# design.net
KiCad netlist of a schematic drawn in Altium Designer
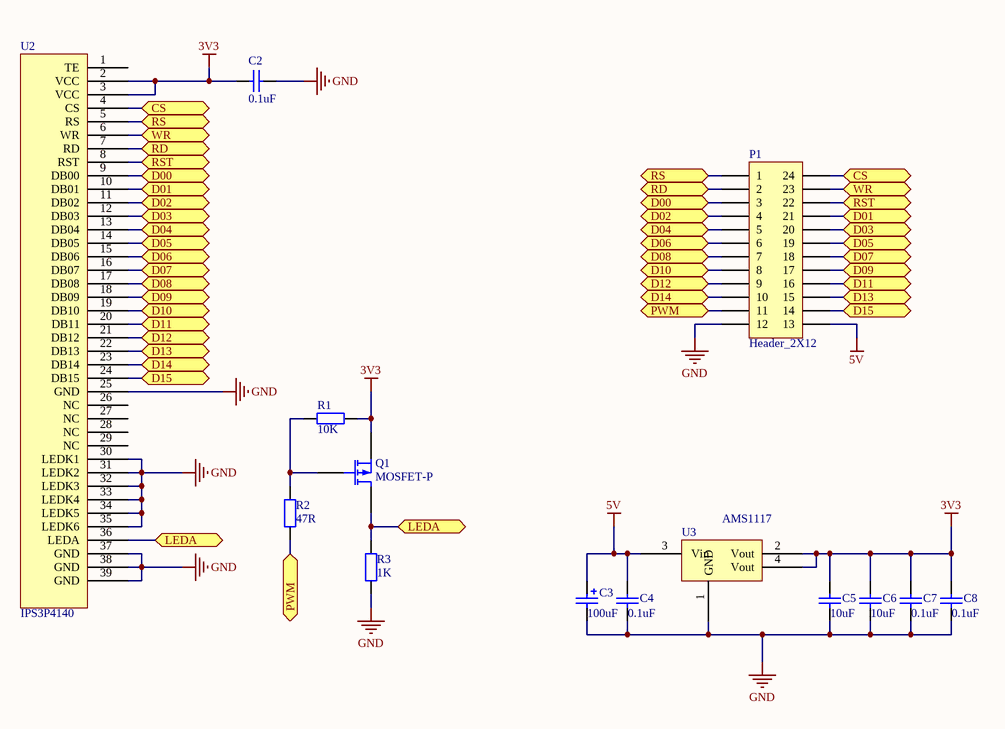
[diagram p0: 液晶板.SchDoc]

(export (version "E")
  (design (tool "Eeschema 10.0.6"))
  (components
    (comp (ref "C2")
      (value "0.1uF")
      (footprint "1608[0603]")
      (description "Capacitor (Semiconductor SIM Model)")
      (fields (field (name "Comment") "Cap Semi") (field (name "PUBLISHER") "Altium Limited"))
      (libsource (lib "Miscellaneous Devices") (part "Cap Semi"))
    )
    (comp (ref "C3")
      (value "100uF")
      (footprint "3528")
      (description "Polarized Capacitor (Axial)")
      (fields (field (name "Comment") "Cap Pol2") (field (name "PUBLISHER") "Altium Limited"))
      (libsource (lib "Miscellaneous Devices") (part "Cap Pol2"))
    )
    (comp (ref "C4")
      (value "0.1uF")
      (footprint "1608[0603]")
      (description "Capacitor (Semiconductor SIM Model)")
      (fields (field (name "Comment") "Cap Semi") (field (name "PUBLISHER") "Altium Limited"))
      (libsource (lib "Miscellaneous Devices") (part "Cap Semi"))
    )
    (comp (ref "C5")
      (value "10uF")
      (footprint "1608[0603]")
      (description "Capacitor (Semiconductor SIM Model)")
      (fields (field (name "Comment") "Cap Semi") (field (name "PUBLISHER") "Altium Limited"))
      (libsource (lib "Miscellaneous Devices") (part "Cap Semi"))
    )
    (comp (ref "C6")
      (value "10uF")
      (footprint "1608[0603]")
      (description "Capacitor (Semiconductor SIM Model)")
      (fields (field (name "Comment") "Cap Semi") (field (name "PUBLISHER") "Altium Limited"))
      (libsource (lib "Miscellaneous Devices") (part "Cap Semi"))
    )
    (comp (ref "C7")
      (value "0.1uF")
      (footprint "1608[0603]")
      (description "Capacitor (Semiconductor SIM Model)")
      (fields (field (name "Comment") "Cap Semi") (field (name "PUBLISHER") "Altium Limited"))
      (libsource (lib "Miscellaneous Devices") (part "Cap Semi"))
    )
    (comp (ref "C8")
      (value "0.1uF")
      (footprint "1608[0603]")
      (description "Capacitor (Semiconductor SIM Model)")
      (fields (field (name "Comment") "Cap Semi") (field (name "PUBLISHER") "Altium Limited"))
      (libsource (lib "Miscellaneous Devices") (part "Cap Semi"))
    )
    (comp (ref "P1") (value "Header_2X12") (footprint "HDR2X12") (libsource (lib "元件") (part "Header_2X12")))
    (comp (ref "Q1")
      (value "MOSFET-P")
      (footprint "SOT23_N")
      (description "P-Channel MOSFET")
      (fields (field (name "PUBLISHER") "Altium Limited"))
      (libsource (lib "Miscellaneous Devices") (part "MOSFET-P"))
    )
    (comp (ref "R1")
      (value "10K")
      (footprint "1608[0603]")
      (description "Resistor")
      (fields (field (name "Comment") "Res2") (field (name "PUBLISHER") "Altium Limited"))
      (libsource (lib "") (part "Res2_1"))
    )
    (comp (ref "R2")
      (value "47R")
      (footprint "1608[0603]")
      (description "Resistor")
      (fields (field (name "Comment") "Res2") (field (name "PUBLISHER") "Altium Limited"))
      (libsource (lib "") (part "Res2_2"))
    )
    (comp (ref "R3")
      (value "1K")
      (footprint "1608[0603]")
      (description "Resistor")
      (fields (field (name "Comment") "Res2") (field (name "PUBLISHER") "Altium Limited"))
      (libsource (lib "Miscellaneous Devices") (part "Res2"))
    )
    (comp (ref "U2")
      (value "IPS3P4140")
      (footprint "FH26-39S-0.3SHW")
      (description "IPS液晶显示屏")
      (libsource (lib "元件") (part "IPS3P4140"))
    )
    (comp (ref "U3")
      (value "AMS1117")
      (footprint "SOT223")
      (description "稳压IC")
      (libsource (lib "元件") (part "AMS1117"))
    )
  )
  (nets
    (net (code "1") (name "/CS") (class "Default")
      (node (ref "P1") (pin "24") (pinfunction "24_24") (pintype "passive"))
      (node (ref "U2") (pin "4") (pinfunction "CS_4") (pintype "passive"))
    )
    (net (code "2") (name "/D00") (class "Default")
      (node (ref "P1") (pin "3") (pinfunction "3_3") (pintype "passive"))
      (node (ref "U2") (pin "9") (pinfunction "DB00_9") (pintype "passive"))
    )
    (net (code "3") (name "/D01") (class "Default")
      (node (ref "P1") (pin "21") (pinfunction "21_21") (pintype "passive"))
      (node (ref "U2") (pin "10") (pinfunction "DB01_10") (pintype "passive"))
    )
    (net (code "4") (name "/D02") (class "Default")
      (node (ref "P1") (pin "4") (pinfunction "4_4") (pintype "passive"))
      (node (ref "U2") (pin "11") (pinfunction "DB02_11") (pintype "passive"))
    )
    (net (code "5") (name "/D03") (class "Default")
      (node (ref "P1") (pin "20") (pinfunction "20_20") (pintype "passive"))
      (node (ref "U2") (pin "12") (pinfunction "DB03_12") (pintype "passive"))
    )
    (net (code "6") (name "/D04") (class "Default")
      (node (ref "P1") (pin "5") (pinfunction "5_5") (pintype "passive"))
      (node (ref "U2") (pin "13") (pinfunction "DB04_13") (pintype "passive"))
    )
    (net (code "7") (name "/D05") (class "Default")
      (node (ref "P1") (pin "19") (pinfunction "19_19") (pintype "passive"))
      (node (ref "U2") (pin "14") (pinfunction "DB05_14") (pintype "passive"))
    )
    (net (code "8") (name "/D06") (class "Default")
      (node (ref "P1") (pin "6") (pinfunction "6_6") (pintype "passive"))
      (node (ref "U2") (pin "15") (pinfunction "DB06_15") (pintype "passive"))
    )
    (net (code "9") (name "/D07") (class "Default")
      (node (ref "P1") (pin "18") (pinfunction "18_18") (pintype "passive"))
      (node (ref "U2") (pin "16") (pinfunction "DB07_16") (pintype "passive"))
    )
    (net (code "10") (name "/D08") (class "Default")
      (node (ref "P1") (pin "7") (pinfunction "7_7") (pintype "passive"))
      (node (ref "U2") (pin "17") (pinfunction "DB08_17") (pintype "passive"))
    )
    (net (code "11") (name "/D09") (class "Default")
      (node (ref "P1") (pin "17") (pinfunction "17_17") (pintype "passive"))
      (node (ref "U2") (pin "18") (pinfunction "DB09_18") (pintype "passive"))
    )
    (net (code "12") (name "/D10") (class "Default")
      (node (ref "P1") (pin "8") (pinfunction "8_8") (pintype "passive"))
      (node (ref "U2") (pin "19") (pinfunction "DB10_19") (pintype "passive"))
    )
    (net (code "13") (name "/D11") (class "Default")
      (node (ref "P1") (pin "16") (pinfunction "16_16") (pintype "passive"))
      (node (ref "U2") (pin "20") (pinfunction "DB11_20") (pintype "passive"))
    )
    (net (code "14") (name "/D12") (class "Default")
      (node (ref "P1") (pin "9") (pinfunction "9_9") (pintype "passive"))
      (node (ref "U2") (pin "21") (pinfunction "DB12_21") (pintype "passive"))
    )
    (net (code "15") (name "/D13") (class "Default")
      (node (ref "P1") (pin "15") (pinfunction "15_15") (pintype "passive"))
      (node (ref "U2") (pin "22") (pinfunction "DB13_22") (pintype "passive"))
    )
    (net (code "16") (name "/D14") (class "Default")
      (node (ref "P1") (pin "10") (pinfunction "10_10") (pintype "passive"))
      (node (ref "U2") (pin "23") (pinfunction "DB14_23") (pintype "passive"))
    )
    (net (code "17") (name "/D15") (class "Default")
      (node (ref "P1") (pin "14") (pinfunction "14_14") (pintype "passive"))
      (node (ref "U2") (pin "24") (pinfunction "DB15_24") (pintype "passive"))
    )
    (net (code "18") (name "/LEDA") (class "Default")
      (node (ref "Q1") (pin "1") (pinfunction "D_1") (pintype "passive"))
      (node (ref "R3") (pin "2") (pinfunction "2_2") (pintype "passive"))
      (node (ref "U2") (pin "36") (pinfunction "LEDA_36") (pintype "passive"))
    )
    (net (code "19") (name "/PWM") (class "Default")
      (node (ref "P1") (pin "11") (pinfunction "11_11") (pintype "passive"))
      (node (ref "R2") (pin "2") (pinfunction "2_2") (pintype "passive"))
    )
    (net (code "20") (name "/RD") (class "Default")
      (node (ref "P1") (pin "2") (pinfunction "2_2") (pintype "passive"))
      (node (ref "U2") (pin "7") (pinfunction "RD_7") (pintype "passive"))
    )
    (net (code "21") (name "/RS") (class "Default")
      (node (ref "P1") (pin "1") (pinfunction "1_1") (pintype "passive"))
      (node (ref "U2") (pin "5") (pinfunction "RS_5") (pintype "passive"))
    )
    (net (code "22") (name "/RST") (class "Default")
      (node (ref "P1") (pin "22") (pinfunction "22_22") (pintype "passive"))
      (node (ref "U2") (pin "8") (pinfunction "RST_8") (pintype "passive"))
    )
    (net (code "23") (name "/WR") (class "Default")
      (node (ref "P1") (pin "23") (pinfunction "23_23") (pintype "passive"))
      (node (ref "U2") (pin "6") (pinfunction "WR_6") (pintype "passive"))
    )
    (net (code "24") (name "3V3") (class "Default")
      (node (ref "C2") (pin "2") (pinfunction "2_2") (pintype "passive"))
      (node (ref "C5") (pin "2") (pinfunction "2_2") (pintype "passive"))
      (node (ref "C6") (pin "2") (pinfunction "2_2") (pintype "passive"))
      (node (ref "C7") (pin "2") (pinfunction "2_2") (pintype "passive"))
      (node (ref "C8") (pin "2") (pinfunction "2_2") (pintype "passive"))
      (node (ref "Q1") (pin "3") (pinfunction "S_3") (pintype "passive"))
      (node (ref "R1") (pin "1") (pinfunction "1_1") (pintype "passive"))
      (node (ref "U2") (pin "2") (pinfunction "VCC_2") (pintype "passive"))
      (node (ref "U2") (pin "3") (pinfunction "VCC_3") (pintype "passive"))
      (node (ref "U3") (pin "2") (pinfunction "Vout_2") (pintype "power_in"))
      (node (ref "U3") (pin "4") (pinfunction "Vout_4") (pintype "passive"))
    )
    (net (code "25") (name "5V") (class "Default")
      (node (ref "C3") (pin "1") (pinfunction "1_1") (pintype "passive"))
      (node (ref "C4") (pin "2") (pinfunction "2_2") (pintype "passive"))
      (node (ref "P1") (pin "13") (pinfunction "13_13") (pintype "passive"))
      (node (ref "U3") (pin "3") (pinfunction "Vin_3") (pintype "passive"))
    )
    (net (code "26") (name "GND") (class "Default")
      (node (ref "C2") (pin "1") (pinfunction "1_1") (pintype "passive"))
      (node (ref "C3") (pin "2") (pinfunction "2_2") (pintype "passive"))
      (node (ref "C4") (pin "1") (pinfunction "1_1") (pintype "passive"))
      (node (ref "C5") (pin "1") (pinfunction "1_1") (pintype "passive"))
      (node (ref "C6") (pin "1") (pinfunction "1_1") (pintype "passive"))
      (node (ref "C7") (pin "1") (pinfunction "1_1") (pintype "passive"))
      (node (ref "C8") (pin "1") (pinfunction "1_1") (pintype "passive"))
      (node (ref "P1") (pin "12") (pinfunction "12_12") (pintype "passive"))
      (node (ref "R3") (pin "1") (pinfunction "1_1") (pintype "passive"))
      (node (ref "U2") (pin "25") (pinfunction "GND_25") (pintype "passive"))
      (node (ref "U2") (pin "30") (pinfunction "LEDK1_30") (pintype "passive"))
      (node (ref "U2") (pin "31") (pinfunction "LEDK2_31") (pintype "passive"))
      (node (ref "U2") (pin "32") (pinfunction "LEDK3_32") (pintype "passive"))
      (node (ref "U2") (pin "33") (pinfunction "LEDK4_33") (pintype "passive"))
      (node (ref "U2") (pin "34") (pinfunction "LEDK5_34") (pintype "passive"))
      (node (ref "U2") (pin "35") (pinfunction "LEDK6_35") (pintype "passive"))
      (node (ref "U2") (pin "37") (pinfunction "GND_37") (pintype "passive"))
      (node (ref "U2") (pin "38") (pinfunction "GND_38") (pintype "passive"))
      (node (ref "U2") (pin "39") (pinfunction "GND_39") (pintype "passive"))
      (node (ref "U3") (pin "1") (pinfunction "GND_1") (pintype "passive"))
    )
    (net (code "27") (name "Net-(Q1-G)") (class "Default")
      (node (ref "Q1") (pin "2") (pinfunction "G_2") (pintype "passive"))
      (node (ref "R1") (pin "2") (pinfunction "2_2") (pintype "passive"))
      (node (ref "R2") (pin "1") (pinfunction "1_1") (pintype "passive"))
    )
    (net (code "28") (name "unconnected-(U2-NC-Pad26)") (class "Default")
      (node (ref "U2") (pin "26") (pinfunction "NC_26") (pintype "passive"))
    )
    (net (code "29") (name "unconnected-(U2-NC-Pad27)") (class "Default")
      (node (ref "U2") (pin "27") (pinfunction "NC_27") (pintype "passive"))
    )
    (net (code "30") (name "unconnected-(U2-NC-Pad28)") (class "Default")
      (node (ref "U2") (pin "28") (pinfunction "NC_28") (pintype "passive"))
    )
    (net (code "31") (name "unconnected-(U2-NC-Pad29)") (class "Default")
      (node (ref "U2") (pin "29") (pinfunction "NC_29") (pintype "passive"))
    )
    (net (code "32") (name "unconnected-(U2-TE-Pad1)") (class "Default")
      (node (ref "U2") (pin "1") (pinfunction "TE_1") (pintype "passive"))
    )
  )
)
